# Driverkort_top.net
KiCad netlist of a schematic drawn in Altium Designer
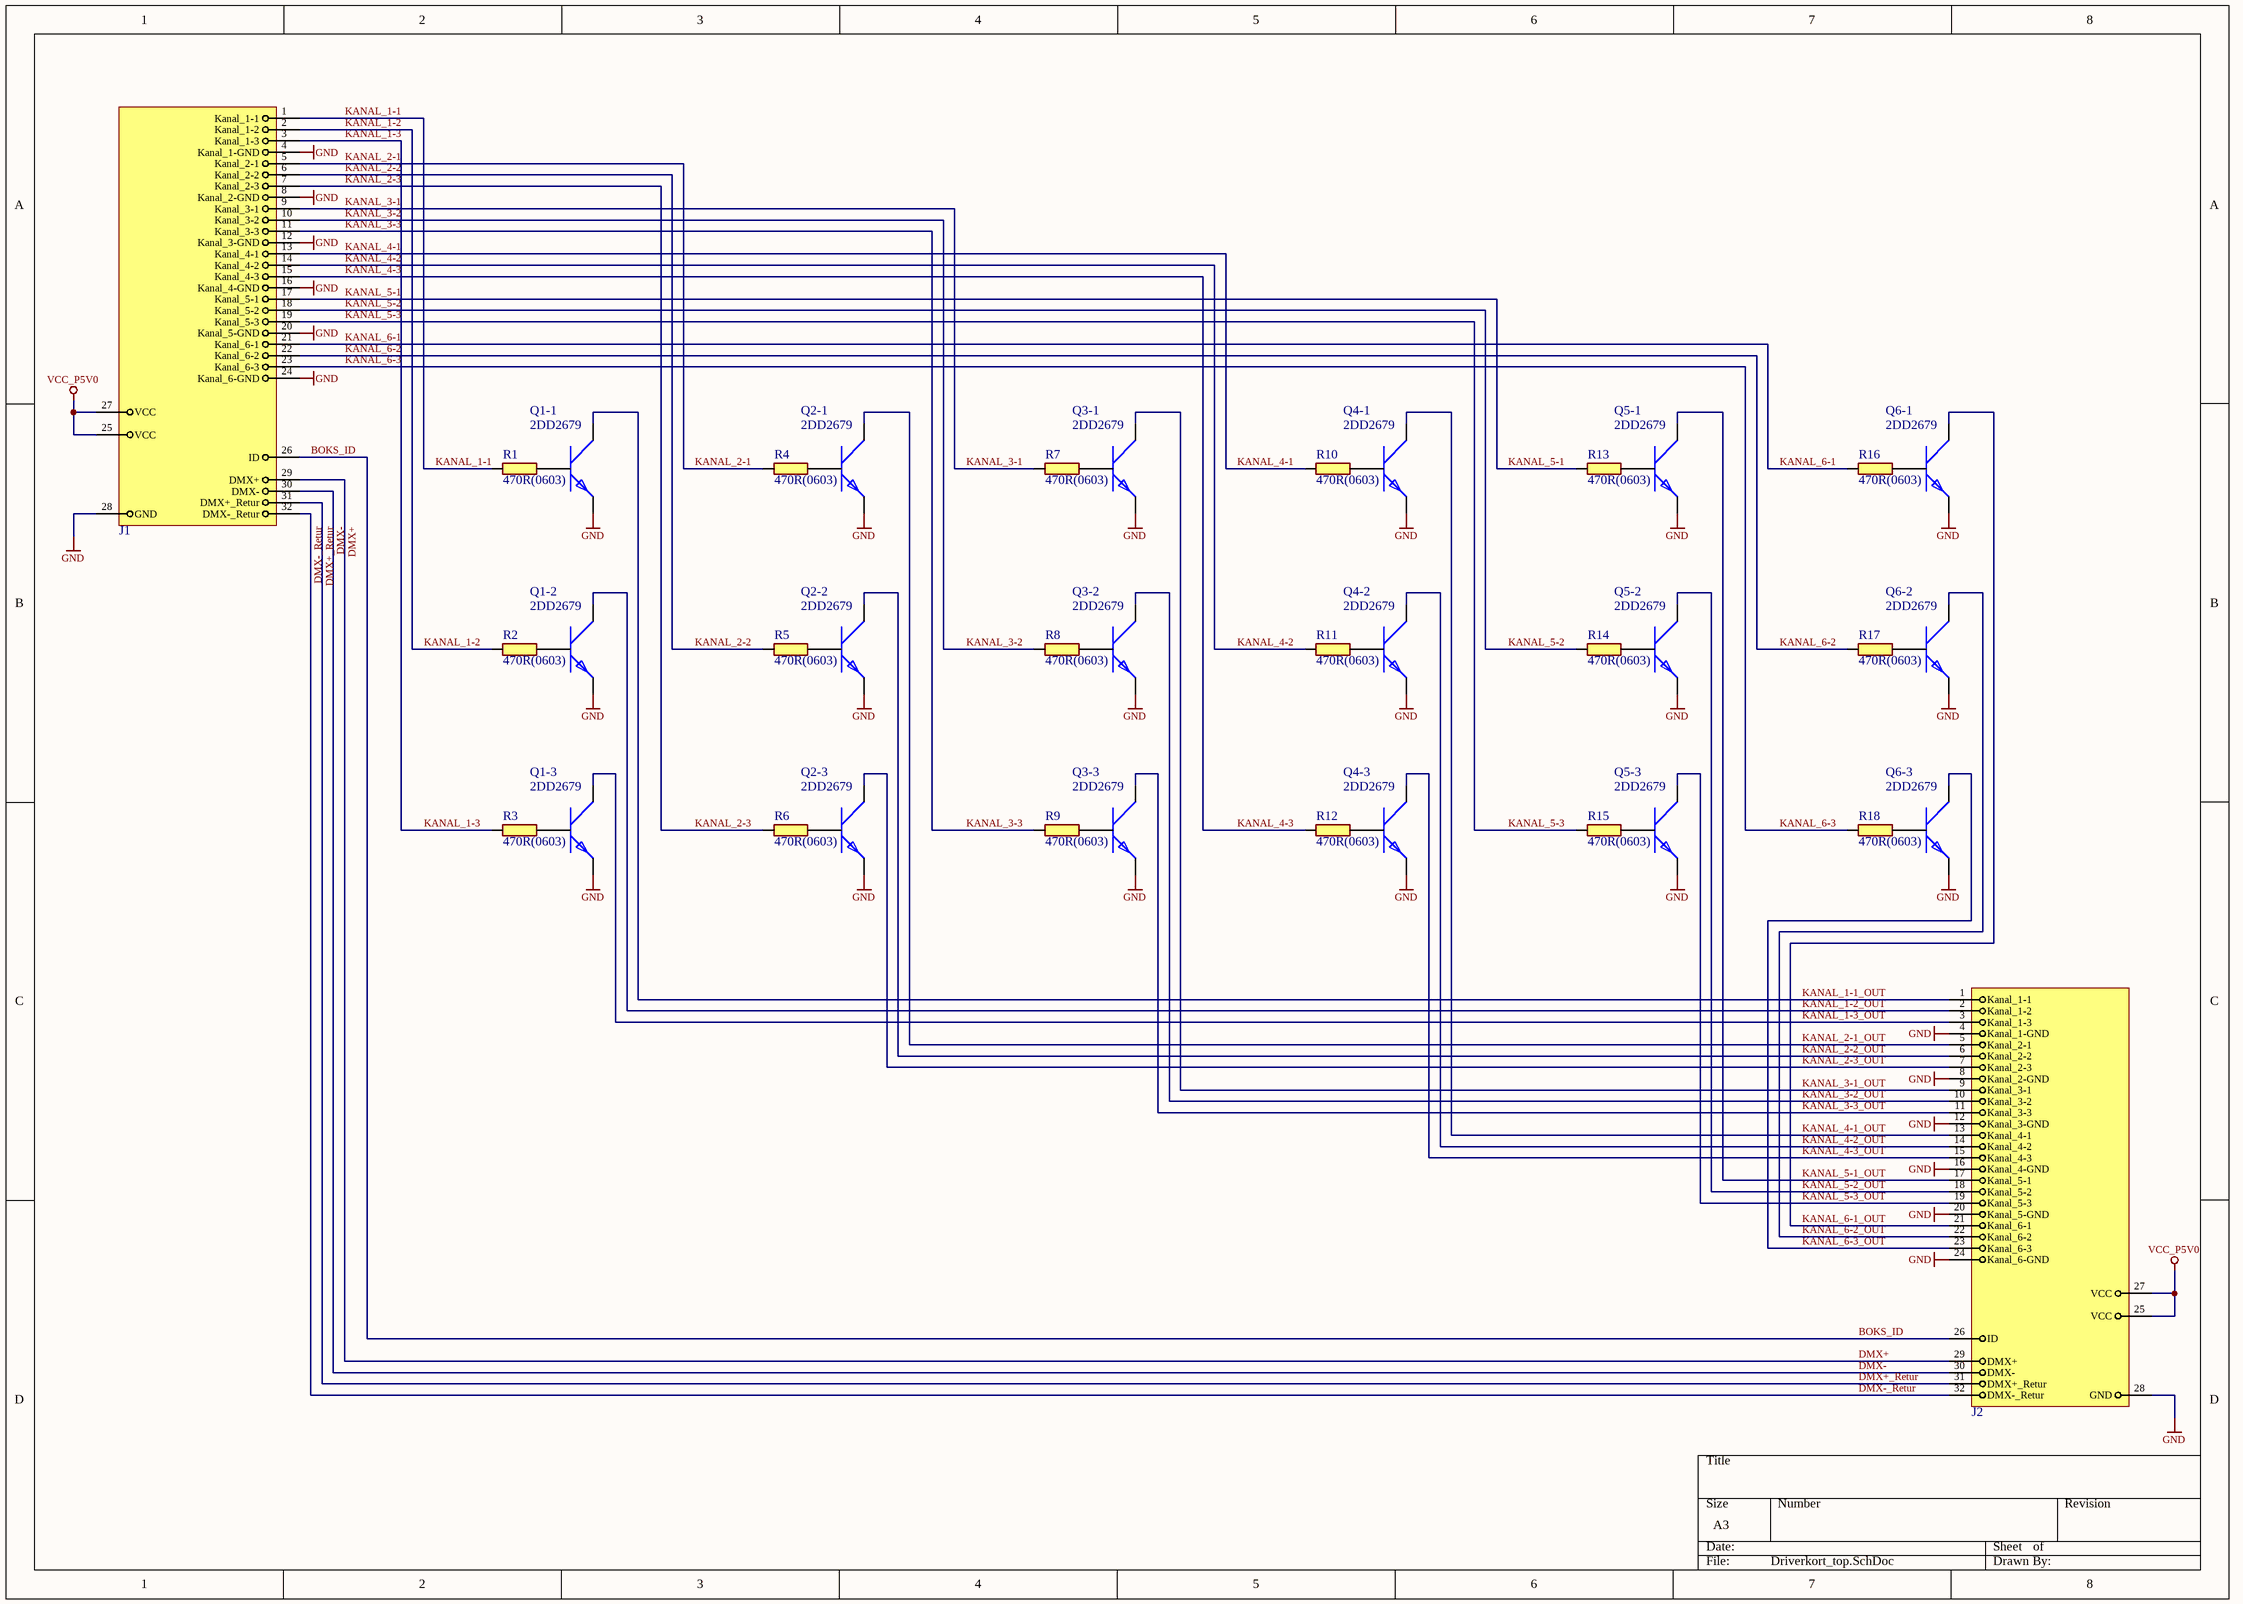
[diagram p0: Driverkort_top.SchDoc]

(export (version "E")
  (design (tool "Eeschema 10.0.6"))
  (components
    (comp (ref "J1")
      (value "Lysreklameparalellbusskontakt2015_FEMALE")
      (footprint "HDRRAF32W64P254_2X16_4064X1260X600B")
      (libsource (lib "Lysreklameparalellbusskontakt2015_FEMALE") (part "Lysreklameparalellbusskontakt2015_FEMALE"))
    )
    (comp (ref "J2")
      (value "Lysreklameparalellbusskontakt2015")
      (footprint "HDRRA32W64P254_2X16_4064X1260X600B")
      (libsource (lib "Lysreklameparalellbusskontakt2015") (part "Lysreklameparalellbusskontakt2015"))
    )
    (comp (ref "Q1-1")
      (value "2DD2679")
      (footprint "SOT89-150P409X160-3N")
      (description "LOW VCE(SAT) NPN SURFACE MOUNT TRANSISTOR")
      (libsource (lib "OVLib") (part "NPN_BCE"))
    )
    (comp (ref "Q1-2")
      (value "2DD2679")
      (footprint "SOT89-150P409X160-3N")
      (description "LOW VCE(SAT) NPN SURFACE MOUNT TRANSISTOR")
      (libsource (lib "OVLib") (part "NPN_BCE"))
    )
    (comp (ref "Q1-3")
      (value "2DD2679")
      (footprint "SOT89-150P409X160-3N")
      (description "LOW VCE(SAT) NPN SURFACE MOUNT TRANSISTOR")
      (libsource (lib "OVLib") (part "NPN_BCE"))
    )
    (comp (ref "Q2-1")
      (value "2DD2679")
      (footprint "SOT89-150P409X160-3N")
      (description "LOW VCE(SAT) NPN SURFACE MOUNT TRANSISTOR")
      (libsource (lib "OVLib") (part "NPN_BCE"))
    )
    (comp (ref "Q2-2")
      (value "2DD2679")
      (footprint "SOT89-150P409X160-3N")
      (description "LOW VCE(SAT) NPN SURFACE MOUNT TRANSISTOR")
      (libsource (lib "OVLib") (part "NPN_BCE"))
    )
    (comp (ref "Q2-3")
      (value "2DD2679")
      (footprint "SOT89-150P409X160-3N")
      (description "LOW VCE(SAT) NPN SURFACE MOUNT TRANSISTOR")
      (libsource (lib "OVLib") (part "NPN_BCE"))
    )
    (comp (ref "Q3-1")
      (value "2DD2679")
      (footprint "SOT89-150P409X160-3N")
      (description "LOW VCE(SAT) NPN SURFACE MOUNT TRANSISTOR")
      (libsource (lib "OVLib") (part "NPN_BCE"))
    )
    (comp (ref "Q3-2")
      (value "2DD2679")
      (footprint "SOT89-150P409X160-3N")
      (description "LOW VCE(SAT) NPN SURFACE MOUNT TRANSISTOR")
      (libsource (lib "OVLib") (part "NPN_BCE"))
    )
    (comp (ref "Q3-3")
      (value "2DD2679")
      (footprint "SOT89-150P409X160-3N")
      (description "LOW VCE(SAT) NPN SURFACE MOUNT TRANSISTOR")
      (libsource (lib "OVLib") (part "NPN_BCE"))
    )
    (comp (ref "Q4-1")
      (value "2DD2679")
      (footprint "SOT89-150P409X160-3N")
      (description "LOW VCE(SAT) NPN SURFACE MOUNT TRANSISTOR")
      (libsource (lib "OVLib") (part "NPN_BCE"))
    )
    (comp (ref "Q4-2")
      (value "2DD2679")
      (footprint "SOT89-150P409X160-3N")
      (description "LOW VCE(SAT) NPN SURFACE MOUNT TRANSISTOR")
      (libsource (lib "OVLib") (part "NPN_BCE"))
    )
    (comp (ref "Q4-3")
      (value "2DD2679")
      (footprint "SOT89-150P409X160-3N")
      (description "LOW VCE(SAT) NPN SURFACE MOUNT TRANSISTOR")
      (libsource (lib "OVLib") (part "NPN_BCE"))
    )
    (comp (ref "Q5-1")
      (value "2DD2679")
      (footprint "SOT89-150P409X160-3N")
      (description "LOW VCE(SAT) NPN SURFACE MOUNT TRANSISTOR")
      (libsource (lib "OVLib") (part "NPN_BCE"))
    )
    (comp (ref "Q5-2")
      (value "2DD2679")
      (footprint "SOT89-150P409X160-3N")
      (description "LOW VCE(SAT) NPN SURFACE MOUNT TRANSISTOR")
      (libsource (lib "OVLib") (part "NPN_BCE"))
    )
    (comp (ref "Q5-3")
      (value "2DD2679")
      (footprint "SOT89-150P409X160-3N")
      (description "LOW VCE(SAT) NPN SURFACE MOUNT TRANSISTOR")
      (libsource (lib "OVLib") (part "NPN_BCE"))
    )
    (comp (ref "Q6-1")
      (value "2DD2679")
      (footprint "SOT89-150P409X160-3N")
      (description "LOW VCE(SAT) NPN SURFACE MOUNT TRANSISTOR")
      (libsource (lib "OVLib") (part "NPN_BCE"))
    )
    (comp (ref "Q6-2")
      (value "2DD2679")
      (footprint "SOT89-150P409X160-3N")
      (description "LOW VCE(SAT) NPN SURFACE MOUNT TRANSISTOR")
      (libsource (lib "OVLib") (part "NPN_BCE"))
    )
    (comp (ref "Q6-3")
      (value "2DD2679")
      (footprint "SOT89-150P409X160-3N")
      (description "LOW VCE(SAT) NPN SURFACE MOUNT TRANSISTOR")
      (libsource (lib "OVLib") (part "NPN_BCE"))
    )
    (comp (ref "R1")
      (value "470R(0603)")
      (footprint "RESC0603(1608)_N")
      (description "470R 0603 0.1W 1% Thick film resistor")
      (libsource (lib "OVLib") (part "Resistor2"))
    )
    (comp (ref "R2")
      (value "470R(0603)")
      (footprint "RESC0603(1608)_N")
      (description "470R 0603 0.1W 1% Thick film resistor")
      (libsource (lib "OVLib") (part "Resistor2"))
    )
    (comp (ref "R3")
      (value "470R(0603)")
      (footprint "RESC0603(1608)_N")
      (description "470R 0603 0.1W 1% Thick film resistor")
      (libsource (lib "OVLib") (part "Resistor2"))
    )
    (comp (ref "R4")
      (value "470R(0603)")
      (footprint "RESC0603(1608)_N")
      (description "470R 0603 0.1W 1% Thick film resistor")
      (libsource (lib "OVLib") (part "Resistor2"))
    )
    (comp (ref "R5")
      (value "470R(0603)")
      (footprint "RESC0603(1608)_N")
      (description "470R 0603 0.1W 1% Thick film resistor")
      (libsource (lib "OVLib") (part "Resistor2"))
    )
    (comp (ref "R6")
      (value "470R(0603)")
      (footprint "RESC0603(1608)_N")
      (description "470R 0603 0.1W 1% Thick film resistor")
      (libsource (lib "OVLib") (part "Resistor2"))
    )
    (comp (ref "R7")
      (value "470R(0603)")
      (footprint "RESC0603(1608)_N")
      (description "470R 0603 0.1W 1% Thick film resistor")
      (libsource (lib "OVLib") (part "Resistor2"))
    )
    (comp (ref "R8")
      (value "470R(0603)")
      (footprint "RESC0603(1608)_N")
      (description "470R 0603 0.1W 1% Thick film resistor")
      (libsource (lib "OVLib") (part "Resistor2"))
    )
    (comp (ref "R9")
      (value "470R(0603)")
      (footprint "RESC0603(1608)_N")
      (description "470R 0603 0.1W 1% Thick film resistor")
      (libsource (lib "OVLib") (part "Resistor2"))
    )
    (comp (ref "R10")
      (value "470R(0603)")
      (footprint "RESC0603(1608)_N")
      (description "470R 0603 0.1W 1% Thick film resistor")
      (libsource (lib "OVLib") (part "Resistor2"))
    )
    (comp (ref "R11")
      (value "470R(0603)")
      (footprint "RESC0603(1608)_N")
      (description "470R 0603 0.1W 1% Thick film resistor")
      (libsource (lib "OVLib") (part "Resistor2"))
    )
    (comp (ref "R12")
      (value "470R(0603)")
      (footprint "RESC0603(1608)_N")
      (description "470R 0603 0.1W 1% Thick film resistor")
      (libsource (lib "OVLib") (part "Resistor2"))
    )
    (comp (ref "R13")
      (value "470R(0603)")
      (footprint "RESC0603(1608)_N")
      (description "470R 0603 0.1W 1% Thick film resistor")
      (libsource (lib "OVLib") (part "Resistor2"))
    )
    (comp (ref "R14")
      (value "470R(0603)")
      (footprint "RESC0603(1608)_N")
      (description "470R 0603 0.1W 1% Thick film resistor")
      (libsource (lib "OVLib") (part "Resistor2"))
    )
    (comp (ref "R15")
      (value "470R(0603)")
      (footprint "RESC0603(1608)_N")
      (description "470R 0603 0.1W 1% Thick film resistor")
      (libsource (lib "OVLib") (part "Resistor2"))
    )
    (comp (ref "R16")
      (value "470R(0603)")
      (footprint "RESC0603(1608)_N")
      (description "470R 0603 0.1W 1% Thick film resistor")
      (libsource (lib "OVLib") (part "Resistor2"))
    )
    (comp (ref "R17")
      (value "470R(0603)")
      (footprint "RESC0603(1608)_N")
      (description "470R 0603 0.1W 1% Thick film resistor")
      (libsource (lib "OVLib") (part "Resistor2"))
    )
    (comp (ref "R18")
      (value "470R(0603)")
      (footprint "RESC0603(1608)_N")
      (description "470R 0603 0.1W 1% Thick film resistor")
      (libsource (lib "OVLib") (part "Resistor2"))
    )
  )
  (nets
    (net (code "1") (name "/BOKS_ID") (class "Default")
      (node (ref "J1") (pin "26") (pinfunction "ID_26") (pintype "passive"))
      (node (ref "J2") (pin "26") (pinfunction "ID_26") (pintype "passive"))
    )
    (net (code "2") (name "/DMX+") (class "Default")
      (node (ref "J1") (pin "29") (pinfunction "DMX+_29") (pintype "passive"))
      (node (ref "J2") (pin "29") (pinfunction "DMX+_29") (pintype "passive"))
    )
    (net (code "3") (name "/DMX+_Retur") (class "Default")
      (node (ref "J1") (pin "31") (pinfunction "DMX+_Retur_31") (pintype "passive"))
      (node (ref "J2") (pin "31") (pinfunction "DMX+_Retur_31") (pintype "passive"))
    )
    (net (code "4") (name "/DMX-") (class "Default")
      (node (ref "J1") (pin "30") (pinfunction "DMX-_30") (pintype "passive"))
      (node (ref "J2") (pin "30") (pinfunction "DMX-_30") (pintype "passive"))
    )
    (net (code "5") (name "/DMX-_Retur") (class "Default")
      (node (ref "J1") (pin "32") (pinfunction "DMX-_Retur_32") (pintype "passive"))
      (node (ref "J2") (pin "32") (pinfunction "DMX-_Retur_32") (pintype "passive"))
    )
    (net (code "6") (name "/KANAL_1-1") (class "Default")
      (node (ref "J1") (pin "1") (pinfunction "Kanal_1-1_1") (pintype "passive"))
      (node (ref "R1") (pin "1") (pinfunction "1_1") (pintype "passive"))
    )
    (net (code "7") (name "/KANAL_1-1_OUT") (class "Default")
      (node (ref "J2") (pin "1") (pinfunction "Kanal_1-1_1") (pintype "passive"))
      (node (ref "Q1-1") (pin "2") (pinfunction "C_2") (pintype "passive"))
    )
    (net (code "8") (name "/KANAL_1-2") (class "Default")
      (node (ref "J1") (pin "2") (pinfunction "Kanal_1-2_2") (pintype "passive"))
      (node (ref "R2") (pin "1") (pinfunction "1_1") (pintype "passive"))
    )
    (net (code "9") (name "/KANAL_1-2_OUT") (class "Default")
      (node (ref "J2") (pin "2") (pinfunction "Kanal_1-2_2") (pintype "passive"))
      (node (ref "Q1-2") (pin "2") (pinfunction "C_2") (pintype "passive"))
    )
    (net (code "10") (name "/KANAL_1-3") (class "Default")
      (node (ref "J1") (pin "3") (pinfunction "Kanal_1-3_3") (pintype "passive"))
      (node (ref "R3") (pin "1") (pinfunction "1_1") (pintype "passive"))
    )
    (net (code "11") (name "/KANAL_1-3_OUT") (class "Default")
      (node (ref "J2") (pin "3") (pinfunction "Kanal_1-3_3") (pintype "passive"))
      (node (ref "Q1-3") (pin "2") (pinfunction "C_2") (pintype "passive"))
    )
    (net (code "12") (name "/KANAL_2-1") (class "Default")
      (node (ref "J1") (pin "5") (pinfunction "Kanal_2-1_5") (pintype "passive"))
      (node (ref "R4") (pin "1") (pinfunction "1_1") (pintype "passive"))
    )
    (net (code "13") (name "/KANAL_2-1_OUT") (class "Default")
      (node (ref "J2") (pin "5") (pinfunction "Kanal_2-1_5") (pintype "passive"))
      (node (ref "Q2-1") (pin "2") (pinfunction "C_2") (pintype "passive"))
    )
    (net (code "14") (name "/KANAL_2-2") (class "Default")
      (node (ref "J1") (pin "6") (pinfunction "Kanal_2-2_6") (pintype "passive"))
      (node (ref "R5") (pin "1") (pinfunction "1_1") (pintype "passive"))
    )
    (net (code "15") (name "/KANAL_2-2_OUT") (class "Default")
      (node (ref "J2") (pin "6") (pinfunction "Kanal_2-2_6") (pintype "passive"))
      (node (ref "Q2-2") (pin "2") (pinfunction "C_2") (pintype "passive"))
    )
    (net (code "16") (name "/KANAL_2-3") (class "Default")
      (node (ref "J1") (pin "7") (pinfunction "Kanal_2-3_7") (pintype "passive"))
      (node (ref "R6") (pin "1") (pinfunction "1_1") (pintype "passive"))
    )
    (net (code "17") (name "/KANAL_2-3_OUT") (class "Default")
      (node (ref "J2") (pin "7") (pinfunction "Kanal_2-3_7") (pintype "passive"))
      (node (ref "Q2-3") (pin "2") (pinfunction "C_2") (pintype "passive"))
    )
    (net (code "18") (name "/KANAL_3-1") (class "Default")
      (node (ref "J1") (pin "9") (pinfunction "Kanal_3-1_9") (pintype "passive"))
      (node (ref "R7") (pin "1") (pinfunction "1_1") (pintype "passive"))
    )
    (net (code "19") (name "/KANAL_3-1_OUT") (class "Default")
      (node (ref "J2") (pin "9") (pinfunction "Kanal_3-1_9") (pintype "passive"))
      (node (ref "Q3-1") (pin "2") (pinfunction "C_2") (pintype "passive"))
    )
    (net (code "20") (name "/KANAL_3-2") (class "Default")
      (node (ref "J1") (pin "10") (pinfunction "Kanal_3-2_10") (pintype "passive"))
      (node (ref "R8") (pin "1") (pinfunction "1_1") (pintype "passive"))
    )
    (net (code "21") (name "/KANAL_3-2_OUT") (class "Default")
      (node (ref "J2") (pin "10") (pinfunction "Kanal_3-2_10") (pintype "passive"))
      (node (ref "Q3-2") (pin "2") (pinfunction "C_2") (pintype "passive"))
    )
    (net (code "22") (name "/KANAL_3-3") (class "Default")
      (node (ref "J1") (pin "11") (pinfunction "Kanal_3-3_11") (pintype "passive"))
      (node (ref "R9") (pin "1") (pinfunction "1_1") (pintype "passive"))
    )
    (net (code "23") (name "/KANAL_3-3_OUT") (class "Default")
      (node (ref "J2") (pin "11") (pinfunction "Kanal_3-3_11") (pintype "passive"))
      (node (ref "Q3-3") (pin "2") (pinfunction "C_2") (pintype "passive"))
    )
    (net (code "24") (name "/KANAL_4-1") (class "Default")
      (node (ref "J1") (pin "13") (pinfunction "Kanal_4-1_13") (pintype "passive"))
      (node (ref "R10") (pin "1") (pinfunction "1_1") (pintype "passive"))
    )
    (net (code "25") (name "/KANAL_4-1_OUT") (class "Default")
      (node (ref "J2") (pin "13") (pinfunction "Kanal_4-1_13") (pintype "passive"))
      (node (ref "Q4-1") (pin "2") (pinfunction "C_2") (pintype "passive"))
    )
    (net (code "26") (name "/KANAL_4-2") (class "Default")
      (node (ref "J1") (pin "14") (pinfunction "Kanal_4-2_14") (pintype "passive"))
      (node (ref "R11") (pin "1") (pinfunction "1_1") (pintype "passive"))
    )
    (net (code "27") (name "/KANAL_4-2_OUT") (class "Default")
      (node (ref "J2") (pin "14") (pinfunction "Kanal_4-2_14") (pintype "passive"))
      (node (ref "Q4-2") (pin "2") (pinfunction "C_2") (pintype "passive"))
    )
    (net (code "28") (name "/KANAL_4-3") (class "Default")
      (node (ref "J1") (pin "15") (pinfunction "Kanal_4-3_15") (pintype "passive"))
      (node (ref "R12") (pin "1") (pinfunction "1_1") (pintype "passive"))
    )
    (net (code "29") (name "/KANAL_4-3_OUT") (class "Default")
      (node (ref "J2") (pin "15") (pinfunction "Kanal_4-3_15") (pintype "passive"))
      (node (ref "Q4-3") (pin "2") (pinfunction "C_2") (pintype "passive"))
    )
    (net (code "30") (name "/KANAL_5-1") (class "Default")
      (node (ref "J1") (pin "17") (pinfunction "Kanal_5-1_17") (pintype "passive"))
      (node (ref "R13") (pin "1") (pinfunction "1_1") (pintype "passive"))
    )
    (net (code "31") (name "/KANAL_5-1_OUT") (class "Default")
      (node (ref "J2") (pin "17") (pinfunction "Kanal_5-1_17") (pintype "passive"))
      (node (ref "Q5-1") (pin "2") (pinfunction "C_2") (pintype "passive"))
    )
    (net (code "32") (name "/KANAL_5-2") (class "Default")
      (node (ref "J1") (pin "18") (pinfunction "Kanal_5-2_18") (pintype "passive"))
      (node (ref "R14") (pin "1") (pinfunction "1_1") (pintype "passive"))
    )
    (net (code "33") (name "/KANAL_5-2_OUT") (class "Default")
      (node (ref "J2") (pin "18") (pinfunction "Kanal_5-2_18") (pintype "passive"))
      (node (ref "Q5-2") (pin "2") (pinfunction "C_2") (pintype "passive"))
    )
    (net (code "34") (name "/KANAL_5-3") (class "Default")
      (node (ref "J1") (pin "19") (pinfunction "Kanal_5-3_19") (pintype "passive"))
      (node (ref "R15") (pin "1") (pinfunction "1_1") (pintype "passive"))
    )
    (net (code "35") (name "/KANAL_5-3_OUT") (class "Default")
      (node (ref "J2") (pin "19") (pinfunction "Kanal_5-3_19") (pintype "passive"))
      (node (ref "Q5-3") (pin "2") (pinfunction "C_2") (pintype "passive"))
    )
    (net (code "36") (name "/KANAL_6-1") (class "Default")
      (node (ref "J1") (pin "21") (pinfunction "Kanal_6-1_21") (pintype "passive"))
      (node (ref "R16") (pin "1") (pinfunction "1_1") (pintype "passive"))
    )
    (net (code "37") (name "/KANAL_6-1_OUT") (class "Default")
      (node (ref "J2") (pin "21") (pinfunction "Kanal_6-1_21") (pintype "passive"))
      (node (ref "Q6-1") (pin "2") (pinfunction "C_2") (pintype "passive"))
    )
    (net (code "38") (name "/KANAL_6-2") (class "Default")
      (node (ref "J1") (pin "22") (pinfunction "Kanal_6-2_22") (pintype "passive"))
      (node (ref "R17") (pin "1") (pinfunction "1_1") (pintype "passive"))
    )
    (net (code "39") (name "/KANAL_6-2_OUT") (class "Default")
      (node (ref "J2") (pin "22") (pinfunction "Kanal_6-2_22") (pintype "passive"))
      (node (ref "Q6-2") (pin "2") (pinfunction "C_2") (pintype "passive"))
    )
    (net (code "40") (name "/KANAL_6-3") (class "Default")
      (node (ref "J1") (pin "23") (pinfunction "Kanal_6-3_23") (pintype "passive"))
      (node (ref "R18") (pin "1") (pinfunction "1_1") (pintype "passive"))
    )
    (net (code "41") (name "/KANAL_6-3_OUT") (class "Default")
      (node (ref "J2") (pin "23") (pinfunction "Kanal_6-3_23") (pintype "passive"))
      (node (ref "Q6-3") (pin "2") (pinfunction "C_2") (pintype "passive"))
    )
    (net (code "42") (name "GND") (class "Default")
      (node (ref "J1") (pin "12") (pinfunction "Kanal_3-GND_12") (pintype "passive"))
      (node (ref "J1") (pin "16") (pinfunction "Kanal_4-GND_16") (pintype "passive"))
      (node (ref "J1") (pin "20") (pinfunction "Kanal_5-GND_20") (pintype "passive"))
      (node (ref "J1") (pin "24") (pinfunction "Kanal_6-GND_24") (pintype "passive"))
      (node (ref "J1") (pin "28") (pinfunction "GND_28") (pintype "passive"))
      (node (ref "J1") (pin "4") (pinfunction "Kanal_1-GND_4") (pintype "passive"))
      (node (ref "J1") (pin "8") (pinfunction "Kanal_2-GND_8") (pintype "passive"))
      (node (ref "J2") (pin "12") (pinfunction "Kanal_3-GND_12") (pintype "passive"))
      (node (ref "J2") (pin "16") (pinfunction "Kanal_4-GND_16") (pintype "passive"))
      (node (ref "J2") (pin "20") (pinfunction "Kanal_5-GND_20") (pintype "passive"))
      (node (ref "J2") (pin "24") (pinfunction "Kanal_6-GND_24") (pintype "passive"))
      (node (ref "J2") (pin "28") (pinfunction "GND_28") (pintype "passive"))
      (node (ref "J2") (pin "4") (pinfunction "Kanal_1-GND_4") (pintype "passive"))
      (node (ref "J2") (pin "8") (pinfunction "Kanal_2-GND_8") (pintype "passive"))
      (node (ref "Q1-1") (pin "3") (pinfunction "E_3") (pintype "passive"))
      (node (ref "Q1-2") (pin "3") (pinfunction "E_3") (pintype "passive"))
      (node (ref "Q1-3") (pin "3") (pinfunction "E_3") (pintype "passive"))
      (node (ref "Q2-1") (pin "3") (pinfunction "E_3") (pintype "passive"))
      (node (ref "Q2-2") (pin "3") (pinfunction "E_3") (pintype "passive"))
      (node (ref "Q2-3") (pin "3") (pinfunction "E_3") (pintype "passive"))
      (node (ref "Q3-1") (pin "3") (pinfunction "E_3") (pintype "passive"))
      (node (ref "Q3-2") (pin "3") (pinfunction "E_3") (pintype "passive"))
      (node (ref "Q3-3") (pin "3") (pinfunction "E_3") (pintype "passive"))
      (node (ref "Q4-1") (pin "3") (pinfunction "E_3") (pintype "passive"))
      (node (ref "Q4-2") (pin "3") (pinfunction "E_3") (pintype "passive"))
      (node (ref "Q4-3") (pin "3") (pinfunction "E_3") (pintype "passive"))
      (node (ref "Q5-1") (pin "3") (pinfunction "E_3") (pintype "passive"))
      (node (ref "Q5-2") (pin "3") (pinfunction "E_3") (pintype "passive"))
      (node (ref "Q5-3") (pin "3") (pinfunction "E_3") (pintype "passive"))
      (node (ref "Q6-1") (pin "3") (pinfunction "E_3") (pintype "passive"))
      (node (ref "Q6-2") (pin "3") (pinfunction "E_3") (pintype "passive"))
      (node (ref "Q6-3") (pin "3") (pinfunction "E_3") (pintype "passive"))
    )
    (net (code "43") (name "Net-(Q1-1-B)") (class "Default")
      (node (ref "Q1-1") (pin "1") (pinfunction "B_1") (pintype "passive"))
      (node (ref "R1") (pin "2") (pinfunction "2_2") (pintype "passive"))
    )
    (net (code "44") (name "Net-(Q1-2-B)") (class "Default")
      (node (ref "Q1-2") (pin "1") (pinfunction "B_1") (pintype "passive"))
      (node (ref "R2") (pin "2") (pinfunction "2_2") (pintype "passive"))
    )
    (net (code "45") (name "Net-(Q1-3-B)") (class "Default")
      (node (ref "Q1-3") (pin "1") (pinfunction "B_1") (pintype "passive"))
      (node (ref "R3") (pin "2") (pinfunction "2_2") (pintype "passive"))
    )
    (net (code "46") (name "Net-(Q2-1-B)") (class "Default")
      (node (ref "Q2-1") (pin "1") (pinfunction "B_1") (pintype "passive"))
      (node (ref "R4") (pin "2") (pinfunction "2_2") (pintype "passive"))
    )
    (net (code "47") (name "Net-(Q2-2-B)") (class "Default")
      (node (ref "Q2-2") (pin "1") (pinfunction "B_1") (pintype "passive"))
      (node (ref "R5") (pin "2") (pinfunction "2_2") (pintype "passive"))
    )
    (net (code "48") (name "Net-(Q2-3-B)") (class "Default")
      (node (ref "Q2-3") (pin "1") (pinfunction "B_1") (pintype "passive"))
      (node (ref "R6") (pin "2") (pinfunction "2_2") (pintype "passive"))
    )
    (net (code "49") (name "Net-(Q3-1-B)") (class "Default")
      (node (ref "Q3-1") (pin "1") (pinfunction "B_1") (pintype "passive"))
      (node (ref "R7") (pin "2") (pinfunction "2_2") (pintype "passive"))
    )
    (net (code "50") (name "Net-(Q3-2-B)") (class "Default")
      (node (ref "Q3-2") (pin "1") (pinfunction "B_1") (pintype "passive"))
      (node (ref "R8") (pin "2") (pinfunction "2_2") (pintype "passive"))
    )
    (net (code "51") (name "Net-(Q3-3-B)") (class "Default")
      (node (ref "Q3-3") (pin "1") (pinfunction "B_1") (pintype "passive"))
      (node (ref "R9") (pin "2") (pinfunction "2_2") (pintype "passive"))
    )
    (net (code "52") (name "Net-(Q4-1-B)") (class "Default")
      (node (ref "Q4-1") (pin "1") (pinfunction "B_1") (pintype "passive"))
      (node (ref "R10") (pin "2") (pinfunction "2_2") (pintype "passive"))
    )
    (net (code "53") (name "Net-(Q4-2-B)") (class "Default")
      (node (ref "Q4-2") (pin "1") (pinfunction "B_1") (pintype "passive"))
      (node (ref "R11") (pin "2") (pinfunction "2_2") (pintype "passive"))
    )
    (net (code "54") (name "Net-(Q4-3-B)") (class "Default")
      (node (ref "Q4-3") (pin "1") (pinfunction "B_1") (pintype "passive"))
      (node (ref "R12") (pin "2") (pinfunction "2_2") (pintype "passive"))
    )
    (net (code "55") (name "Net-(Q5-1-B)") (class "Default")
      (node (ref "Q5-1") (pin "1") (pinfunction "B_1") (pintype "passive"))
      (node (ref "R13") (pin "2") (pinfunction "2_2") (pintype "passive"))
    )
    (net (code "56") (name "Net-(Q5-2-B)") (class "Default")
      (node (ref "Q5-2") (pin "1") (pinfunction "B_1") (pintype "passive"))
      (node (ref "R14") (pin "2") (pinfunction "2_2") (pintype "passive"))
    )
    (net (code "57") (name "Net-(Q5-3-B)") (class "Default")
      (node (ref "Q5-3") (pin "1") (pinfunction "B_1") (pintype "passive"))
      (node (ref "R15") (pin "2") (pinfunction "2_2") (pintype "passive"))
    )
    (net (code "58") (name "Net-(Q6-1-B)") (class "Default")
      (node (ref "Q6-1") (pin "1") (pinfunction "B_1") (pintype "passive"))
      (node (ref "R16") (pin "2") (pinfunction "2_2") (pintype "passive"))
    )
    (net (code "59") (name "Net-(Q6-2-B)") (class "Default")
      (node (ref "Q6-2") (pin "1") (pinfunction "B_1") (pintype "passive"))
      (node (ref "R17") (pin "2") (pinfunction "2_2") (pintype "passive"))
    )
    (net (code "60") (name "Net-(Q6-3-B)") (class "Default")
      (node (ref "Q6-3") (pin "1") (pinfunction "B_1") (pintype "passive"))
      (node (ref "R18") (pin "2") (pinfunction "2_2") (pintype "passive"))
    )
    (net (code "61") (name "VCC_P5V0") (class "Default")
      (node (ref "J1") (pin "25") (pinfunction "VCC_25") (pintype "passive"))
      (node (ref "J1") (pin "27") (pinfunction "VCC_27") (pintype "passive"))
      (node (ref "J2") (pin "25") (pinfunction "VCC_25") (pintype "passive"))
      (node (ref "J2") (pin "27") (pinfunction "VCC_27") (pintype "passive"))
    )
  )
)
